# GCtoUSB_Current.net
KiCad netlist of a schematic drawn in EAGLE
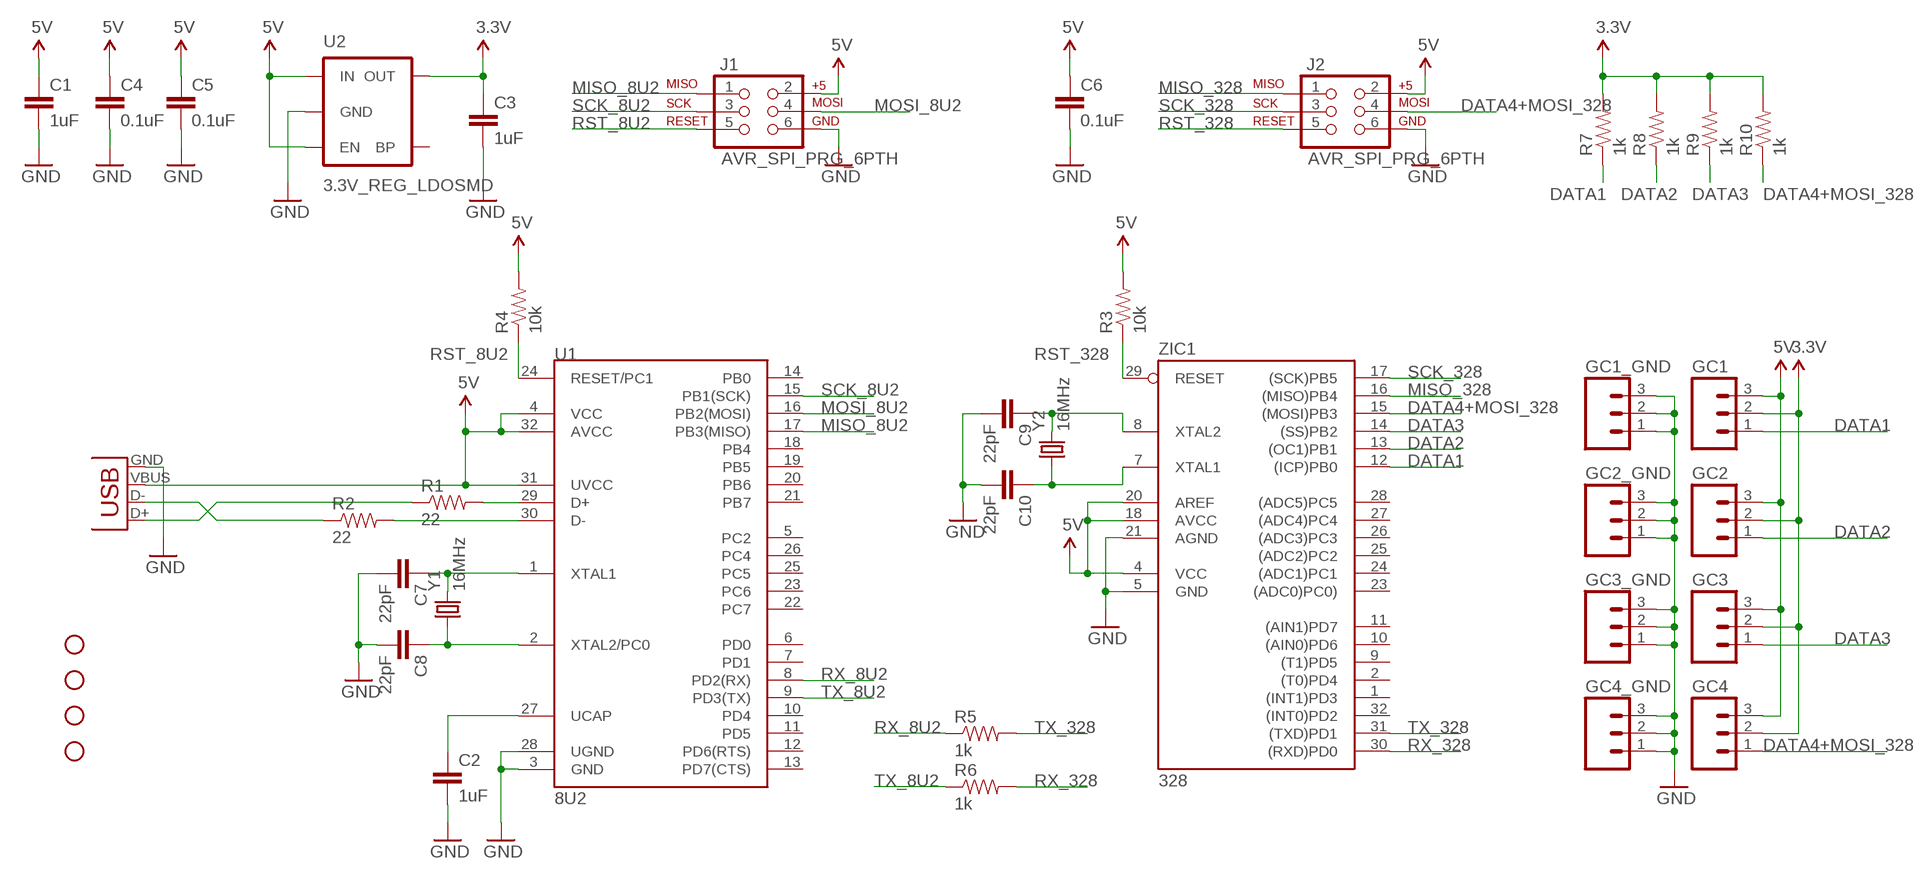
[diagram p0: schematic, sheet 1]

(export (version "E")
  (design (tool "Eeschema 10.0.6"))
  (components
    (comp (ref "C1")
      (value "1uF")
      (footprint "eagle-import:0402-CAP")
      (libsource (lib "eagle-import") (part "CAP0402-CAP"))
    )
    (comp (ref "C2")
      (value "1uF")
      (footprint "eagle-import:0402-CAP")
      (libsource (lib "eagle-import") (part "CAP0402-CAP"))
    )
    (comp (ref "C3")
      (value "1uF")
      (footprint "eagle-import:0402-CAP")
      (libsource (lib "eagle-import") (part "CAP0402-CAP"))
    )
    (comp (ref "C4")
      (value "0.1uF")
      (footprint "eagle-import:0402-CAP")
      (libsource (lib "eagle-import") (part "CAP0402-CAP"))
    )
    (comp (ref "C5")
      (value "0.1uF")
      (footprint "eagle-import:0402-CAP")
      (libsource (lib "eagle-import") (part "CAP0402-CAP"))
    )
    (comp (ref "C6")
      (value "0.1uF")
      (footprint "eagle-import:0402-CAP")
      (libsource (lib "eagle-import") (part "CAP0402-CAP"))
    )
    (comp (ref "C7")
      (value "22pF")
      (footprint "eagle-import:0402-CAP")
      (libsource (lib "eagle-import") (part "CAP0402-CAP"))
    )
    (comp (ref "C8")
      (value "22pF")
      (footprint "eagle-import:0402-CAP")
      (libsource (lib "eagle-import") (part "CAP0402-CAP"))
    )
    (comp (ref "C9")
      (value "22pF")
      (footprint "eagle-import:0402-CAP")
      (libsource (lib "eagle-import") (part "CAP0402-CAP"))
    )
    (comp (ref "C10")
      (value "22pF")
      (footprint "eagle-import:0402-CAP")
      (libsource (lib "eagle-import") (part "CAP0402-CAP"))
    )
    (comp (ref "GC1")
      (value "M031X03_NO_SILK")
      (footprint "eagle-import:1X03_NO_SILK")
      (libsource (lib "eagle-import") (part "M031X03_NO_SILK"))
    )
    (comp (ref "GC1_GND")
      (value "M031X03_NO_SILK")
      (footprint "eagle-import:1X03_NO_SILK")
      (libsource (lib "eagle-import") (part "M031X03_NO_SILK"))
    )
    (comp (ref "GC2")
      (value "M031X03_NO_SILK")
      (footprint "eagle-import:1X03_NO_SILK")
      (libsource (lib "eagle-import") (part "M031X03_NO_SILK"))
    )
    (comp (ref "GC2_GND")
      (value "M031X03_NO_SILK")
      (footprint "eagle-import:1X03_NO_SILK")
      (libsource (lib "eagle-import") (part "M031X03_NO_SILK"))
    )
    (comp (ref "GC3")
      (value "M031X03_NO_SILK")
      (footprint "eagle-import:1X03_NO_SILK")
      (libsource (lib "eagle-import") (part "M031X03_NO_SILK"))
    )
    (comp (ref "GC3_GND")
      (value "M031X03_NO_SILK")
      (footprint "eagle-import:1X03_NO_SILK")
      (libsource (lib "eagle-import") (part "M031X03_NO_SILK"))
    )
    (comp (ref "GC4")
      (value "M031X03_NO_SILK")
      (footprint "eagle-import:1X03_NO_SILK")
      (libsource (lib "eagle-import") (part "M031X03_NO_SILK"))
    )
    (comp (ref "GC4_GND")
      (value "M031X03_NO_SILK")
      (footprint "eagle-import:1X03_NO_SILK")
      (libsource (lib "eagle-import") (part "M031X03_NO_SILK"))
    )
    (comp (ref "J1")
      (value "AVR_SPI_PRG_6PTH")
      (footprint "eagle-import:2X3")
      (libsource (lib "eagle-import") (part "AVR_SPI_PRG_6PTH"))
    )
    (comp (ref "J2")
      (value "AVR_SPI_PRG_6PTH")
      (footprint "eagle-import:2X3")
      (libsource (lib "eagle-import") (part "AVR_SPI_PRG_6PTH"))
    )
    (comp (ref "JP5")
      (value "STAND-OFF")
      (footprint "eagle-import:STAND-OFF")
      (libsource (lib "eagle-import") (part "STAND-OFF"))
    )
    (comp (ref "JP6")
      (value "STAND-OFF")
      (footprint "eagle-import:STAND-OFF")
      (libsource (lib "eagle-import") (part "STAND-OFF"))
    )
    (comp (ref "JP7")
      (value "STAND-OFF")
      (footprint "eagle-import:STAND-OFF")
      (libsource (lib "eagle-import") (part "STAND-OFF"))
    )
    (comp (ref "JP8")
      (value "STAND-OFF")
      (footprint "eagle-import:STAND-OFF")
      (libsource (lib "eagle-import") (part "STAND-OFF"))
    )
    (comp (ref "R1")
      (value "22")
      (footprint "eagle-import:0603-RES")
      (libsource (lib "eagle-import") (part "RESISTOR0603-RES"))
    )
    (comp (ref "R2")
      (value "22")
      (footprint "eagle-import:0603-RES")
      (libsource (lib "eagle-import") (part "RESISTOR0603-RES"))
    )
    (comp (ref "R3")
      (value "10k")
      (footprint "eagle-import:0603-RES")
      (libsource (lib "eagle-import") (part "RESISTOR0603-RES"))
    )
    (comp (ref "R4")
      (value "10k")
      (footprint "eagle-import:0603-RES")
      (libsource (lib "eagle-import") (part "RESISTOR0603-RES"))
    )
    (comp (ref "R5")
      (value "1k")
      (footprint "eagle-import:0603-RES")
      (libsource (lib "eagle-import") (part "RESISTOR0603-RES"))
    )
    (comp (ref "R6")
      (value "1k")
      (footprint "eagle-import:0603-RES")
      (libsource (lib "eagle-import") (part "RESISTOR0603-RES"))
    )
    (comp (ref "R7")
      (value "1k")
      (footprint "eagle-import:0603-RES")
      (libsource (lib "eagle-import") (part "RESISTOR0603-RES"))
    )
    (comp (ref "R8")
      (value "1k")
      (footprint "eagle-import:0603-RES")
      (libsource (lib "eagle-import") (part "RESISTOR0603-RES"))
    )
    (comp (ref "R9")
      (value "1k")
      (footprint "eagle-import:0603-RES")
      (libsource (lib "eagle-import") (part "RESISTOR0603-RES"))
    )
    (comp (ref "R10")
      (value "1k")
      (footprint "eagle-import:0603-RES")
      (libsource (lib "eagle-import") (part "RESISTOR0603-RES"))
    )
    (comp (ref "U1")
      (value "8U2")
      (footprint "eagle-import:TQFP32-08")
      (libsource (lib "eagle-import") (part "ATMEGA8U2AU"))
    )
    (comp (ref "U2")
      (value "3.3V_REG_LDOSMD")
      (footprint "eagle-import:SOT23-5")
      (libsource (lib "eagle-import") (part "V_REG_LDOSMD"))
    )
    (comp (ref "X1")
      (value "USB-MB-H")
      (footprint "eagle-import:USB-MB-H")
      (libsource (lib "eagle-import") (part "USB-MB-H"))
    )
    (comp (ref "Y1")
      (value "16MHz")
      (footprint "eagle-import:HC49US")
      (libsource (lib "eagle-import") (part "CRYSTALHC49US"))
    )
    (comp (ref "Y2")
      (value "16MHz")
      (footprint "eagle-import:HC49US")
      (libsource (lib "eagle-import") (part "CRYSTALHC49US"))
    )
    (comp (ref "ZIC1")
      (value "328")
      (footprint "eagle-import:TQFP32-08")
      (libsource (lib "eagle-import") (part "AT90S4433A"))
    )
  )
  (nets
    (net (code "1") (name "/DATA1") (class "Default")
      (node (ref "GC1") (pin "1") (pinfunction "1_1") (pintype "passive"))
      (node (ref "R7") (pin "1") (pinfunction "1_1") (pintype "passive"))
      (node (ref "ZIC1") (pin "12") (pinfunction "(ICP)PB0_12") (pintype "bidirectional"))
    )
    (net (code "2") (name "/DATA2") (class "Default")
      (node (ref "GC2") (pin "1") (pinfunction "1_1") (pintype "passive"))
      (node (ref "R8") (pin "1") (pinfunction "1_1") (pintype "passive"))
      (node (ref "ZIC1") (pin "13") (pinfunction "(OC1)PB1_13") (pintype "bidirectional"))
    )
    (net (code "3") (name "/DATA3") (class "Default")
      (node (ref "GC3") (pin "1") (pinfunction "1_1") (pintype "passive"))
      (node (ref "R9") (pin "1") (pinfunction "1_1") (pintype "passive"))
      (node (ref "ZIC1") (pin "14") (pinfunction "(SS)PB2_14") (pintype "bidirectional"))
    )
    (net (code "4") (name "/DATA4+MOSI_328") (class "Default")
      (node (ref "GC4") (pin "1") (pinfunction "1_1") (pintype "passive"))
      (node (ref "J2") (pin "4") (pinfunction "4_4") (pintype "passive"))
      (node (ref "R10") (pin "1") (pinfunction "1_1") (pintype "passive"))
      (node (ref "ZIC1") (pin "15") (pinfunction "(MOSI)PB3_15") (pintype "bidirectional"))
    )
    (net (code "5") (name "/MISO_8U2") (class "Default")
      (node (ref "J1") (pin "1") (pinfunction "1_1") (pintype "passive"))
      (node (ref "U1") (pin "17") (pinfunction "PB3(MISO)_17") (pintype "bidirectional"))
    )
    (net (code "6") (name "/MISO_328") (class "Default")
      (node (ref "J2") (pin "1") (pinfunction "1_1") (pintype "passive"))
      (node (ref "ZIC1") (pin "16") (pinfunction "(MISO)PB4_16") (pintype "bidirectional"))
    )
    (net (code "7") (name "/MOSI_8U2") (class "Default")
      (node (ref "J1") (pin "4") (pinfunction "4_4") (pintype "passive"))
      (node (ref "U1") (pin "16") (pinfunction "PB2(MOSI)_16") (pintype "bidirectional"))
    )
    (net (code "8") (name "/RST_8U2") (class "Default")
      (node (ref "J1") (pin "5") (pinfunction "5_5") (pintype "passive"))
      (node (ref "R4") (pin "1") (pinfunction "1_1") (pintype "passive"))
      (node (ref "U1") (pin "24") (pinfunction "RESET/PC1_24") (pintype "bidirectional"))
    )
    (net (code "9") (name "/RST_328") (class "Default")
      (node (ref "J2") (pin "5") (pinfunction "5_5") (pintype "passive"))
      (node (ref "R3") (pin "1") (pinfunction "1_1") (pintype "passive"))
      (node (ref "ZIC1") (pin "29") (pinfunction "RESET_29") (pintype "input"))
    )
    (net (code "10") (name "/RX_8U2") (class "Default")
      (node (ref "R5") (pin "1") (pinfunction "1_1") (pintype "passive"))
      (node (ref "U1") (pin "8") (pinfunction "PD2(RX)_8") (pintype "bidirectional"))
    )
    (net (code "11") (name "/RX_328") (class "Default")
      (node (ref "R6") (pin "2") (pinfunction "2_2") (pintype "passive"))
      (node (ref "ZIC1") (pin "30") (pinfunction "(RXD)PD0_30") (pintype "bidirectional"))
    )
    (net (code "12") (name "/SCK_8U2") (class "Default")
      (node (ref "J1") (pin "3") (pinfunction "3_3") (pintype "passive"))
      (node (ref "U1") (pin "15") (pinfunction "PB1(SCK)_15") (pintype "bidirectional"))
    )
    (net (code "13") (name "/SCK_328") (class "Default")
      (node (ref "J2") (pin "3") (pinfunction "3_3") (pintype "passive"))
      (node (ref "ZIC1") (pin "17") (pinfunction "(SCK)PB5_17") (pintype "bidirectional"))
    )
    (net (code "14") (name "/TX_8U2") (class "Default")
      (node (ref "R6") (pin "1") (pinfunction "1_1") (pintype "passive"))
      (node (ref "U1") (pin "9") (pinfunction "PD3(TX)_9") (pintype "bidirectional"))
    )
    (net (code "15") (name "/TX_328") (class "Default")
      (node (ref "R5") (pin "2") (pinfunction "2_2") (pintype "passive"))
      (node (ref "ZIC1") (pin "31") (pinfunction "(TXD)PD1_31") (pintype "bidirectional"))
    )
    (net (code "16") (name "3.3V") (class "Default")
      (node (ref "C3") (pin "1") (pinfunction "1_1") (pintype "passive"))
      (node (ref "GC1") (pin "2") (pinfunction "2_2") (pintype "passive"))
      (node (ref "GC2") (pin "2") (pinfunction "2_2") (pintype "passive"))
      (node (ref "GC3") (pin "2") (pinfunction "2_2") (pintype "passive"))
      (node (ref "GC4") (pin "2") (pinfunction "2_2") (pintype "passive"))
      (node (ref "R10") (pin "2") (pinfunction "2_2") (pintype "passive"))
      (node (ref "R7") (pin "2") (pinfunction "2_2") (pintype "passive"))
      (node (ref "R8") (pin "2") (pinfunction "2_2") (pintype "passive"))
      (node (ref "R9") (pin "2") (pinfunction "2_2") (pintype "passive"))
      (node (ref "U2") (pin "5") (pinfunction "OUT_5") (pintype "passive"))
    )
    (net (code "17") (name "5V") (class "Default")
      (node (ref "C1") (pin "1") (pinfunction "1_1") (pintype "passive"))
      (node (ref "C4") (pin "1") (pinfunction "1_1") (pintype "passive"))
      (node (ref "C5") (pin "1") (pinfunction "1_1") (pintype "passive"))
      (node (ref "C6") (pin "1") (pinfunction "1_1") (pintype "passive"))
      (node (ref "GC1") (pin "3") (pinfunction "3_3") (pintype "passive"))
      (node (ref "GC2") (pin "3") (pinfunction "3_3") (pintype "passive"))
      (node (ref "GC3") (pin "3") (pinfunction "3_3") (pintype "passive"))
      (node (ref "GC4") (pin "3") (pinfunction "3_3") (pintype "passive"))
      (node (ref "J1") (pin "2") (pinfunction "2_2") (pintype "passive"))
      (node (ref "J2") (pin "2") (pinfunction "2_2") (pintype "passive"))
      (node (ref "R3") (pin "2") (pinfunction "2_2") (pintype "passive"))
      (node (ref "R4") (pin "2") (pinfunction "2_2") (pintype "passive"))
      (node (ref "U1") (pin "31") (pinfunction "UVCC_31") (pintype "bidirectional"))
      (node (ref "U1") (pin "32") (pinfunction "AVCC_32") (pintype "bidirectional"))
      (node (ref "U1") (pin "4") (pinfunction "VCC_4") (pintype "bidirectional"))
      (node (ref "U2") (pin "1") (pinfunction "IN_1") (pintype "input"))
      (node (ref "U2") (pin "3") (pinfunction "EN_3") (pintype "input"))
      (node (ref "X1") (pin "VBUS") (pinfunction "VBUS_VBUS") (pintype "bidirectional"))
      (node (ref "ZIC1") (pin "18") (pinfunction "AVCC_18") (pintype "power_in"))
      (node (ref "ZIC1") (pin "20") (pinfunction "AREF_20") (pintype "passive"))
      (node (ref "ZIC1") (pin "4") (pinfunction "VCC_4") (pintype "power_in"))
    )
    (net (code "18") (name "GND") (class "Default")
      (node (ref "C1") (pin "2") (pinfunction "2_2") (pintype "passive"))
      (node (ref "C10") (pin "2") (pinfunction "2_2") (pintype "passive"))
      (node (ref "C2") (pin "2") (pinfunction "2_2") (pintype "passive"))
      (node (ref "C3") (pin "2") (pinfunction "2_2") (pintype "passive"))
      (node (ref "C4") (pin "2") (pinfunction "2_2") (pintype "passive"))
      (node (ref "C5") (pin "2") (pinfunction "2_2") (pintype "passive"))
      (node (ref "C6") (pin "2") (pinfunction "2_2") (pintype "passive"))
      (node (ref "C7") (pin "2") (pinfunction "2_2") (pintype "passive"))
      (node (ref "C8") (pin "2") (pinfunction "2_2") (pintype "passive"))
      (node (ref "C9") (pin "2") (pinfunction "2_2") (pintype "passive"))
      (node (ref "GC1_GND") (pin "1") (pinfunction "1_1") (pintype "passive"))
      (node (ref "GC1_GND") (pin "2") (pinfunction "2_2") (pintype "passive"))
      (node (ref "GC1_GND") (pin "3") (pinfunction "3_3") (pintype "passive"))
      (node (ref "GC2_GND") (pin "1") (pinfunction "1_1") (pintype "passive"))
      (node (ref "GC2_GND") (pin "2") (pinfunction "2_2") (pintype "passive"))
      (node (ref "GC2_GND") (pin "3") (pinfunction "3_3") (pintype "passive"))
      (node (ref "GC3_GND") (pin "1") (pinfunction "1_1") (pintype "passive"))
      (node (ref "GC3_GND") (pin "2") (pinfunction "2_2") (pintype "passive"))
      (node (ref "GC3_GND") (pin "3") (pinfunction "3_3") (pintype "passive"))
      (node (ref "GC4_GND") (pin "1") (pinfunction "1_1") (pintype "passive"))
      (node (ref "GC4_GND") (pin "2") (pinfunction "2_2") (pintype "passive"))
      (node (ref "GC4_GND") (pin "3") (pinfunction "3_3") (pintype "passive"))
      (node (ref "J1") (pin "6") (pinfunction "6_6") (pintype "passive"))
      (node (ref "J2") (pin "6") (pinfunction "6_6") (pintype "passive"))
      (node (ref "U1") (pin "28") (pinfunction "UGND_28") (pintype "bidirectional"))
      (node (ref "U1") (pin "3") (pinfunction "GND_3") (pintype "bidirectional"))
      (node (ref "U2") (pin "2") (pinfunction "GND_2") (pintype "input"))
      (node (ref "X1") (pin "GND") (pinfunction "GND_GND") (pintype "bidirectional"))
      (node (ref "ZIC1") (pin "21") (pinfunction "AGND_21") (pintype "power_in"))
      (node (ref "ZIC1") (pin "5") (pinfunction "GND_5") (pintype "power_in"))
    )
    (net (code "19") (name "Net-(R1-Pad1)") (class "Default")
      (node (ref "R1") (pin "1") (pinfunction "1_1") (pintype "passive"))
      (node (ref "X1") (pin "D+") (pinfunction "D+_D+") (pintype "bidirectional"))
    )
    (net (code "20") (name "Net-(R2-Pad1)") (class "Default")
      (node (ref "R2") (pin "1") (pinfunction "1_1") (pintype "passive"))
      (node (ref "X1") (pin "D-") (pinfunction "D-_D-") (pintype "bidirectional"))
    )
    (net (code "21") (name "Net-(U1-D+)") (class "Default")
      (node (ref "R1") (pin "2") (pinfunction "2_2") (pintype "passive"))
      (node (ref "U1") (pin "29") (pinfunction "D+_29") (pintype "bidirectional"))
    )
    (net (code "22") (name "Net-(U1-D-)") (class "Default")
      (node (ref "R2") (pin "2") (pinfunction "2_2") (pintype "passive"))
      (node (ref "U1") (pin "30") (pinfunction "D-_30") (pintype "bidirectional"))
    )
    (net (code "23") (name "Net-(U1-UCAP)") (class "Default")
      (node (ref "C2") (pin "1") (pinfunction "1_1") (pintype "passive"))
      (node (ref "U1") (pin "27") (pinfunction "UCAP_27") (pintype "bidirectional"))
    )
    (net (code "24") (name "Net-(U1-XTAL1)") (class "Default")
      (node (ref "C7") (pin "1") (pinfunction "1_1") (pintype "passive"))
      (node (ref "U1") (pin "1") (pinfunction "XTAL1_1") (pintype "bidirectional"))
      (node (ref "Y1") (pin "2") (pinfunction "2_2") (pintype "passive"))
    )
    (net (code "25") (name "Net-(U1-XTAL2{slash}PC0)") (class "Default")
      (node (ref "C8") (pin "1") (pinfunction "1_1") (pintype "passive"))
      (node (ref "U1") (pin "2") (pinfunction "XTAL2/PC0_2") (pintype "bidirectional"))
      (node (ref "Y1") (pin "1") (pinfunction "1_1") (pintype "passive"))
    )
    (net (code "26") (name "Net-(ZIC1-XTAL1)") (class "Default")
      (node (ref "C10") (pin "1") (pinfunction "1_1") (pintype "passive"))
      (node (ref "Y2") (pin "1") (pinfunction "1_1") (pintype "passive"))
      (node (ref "ZIC1") (pin "7") (pinfunction "XTAL1_7") (pintype "bidirectional"))
    )
    (net (code "27") (name "Net-(ZIC1-XTAL2)") (class "Default")
      (node (ref "C9") (pin "1") (pinfunction "1_1") (pintype "passive"))
      (node (ref "Y2") (pin "2") (pinfunction "2_2") (pintype "passive"))
      (node (ref "ZIC1") (pin "8") (pinfunction "XTAL2_8") (pintype "bidirectional"))
    )
    (net (code "28") (name "unconnected-(U1-PB0-Pad14)") (class "Default")
      (node (ref "U1") (pin "14") (pinfunction "PB0_14") (pintype "bidirectional"))
    )
    (net (code "29") (name "unconnected-(U1-PB4-Pad18)") (class "Default")
      (node (ref "U1") (pin "18") (pinfunction "PB4_18") (pintype "bidirectional"))
    )
    (net (code "30") (name "unconnected-(U1-PB5-Pad19)") (class "Default")
      (node (ref "U1") (pin "19") (pinfunction "PB5_19") (pintype "bidirectional"))
    )
    (net (code "31") (name "unconnected-(U1-PB6-Pad20)") (class "Default")
      (node (ref "U1") (pin "20") (pinfunction "PB6_20") (pintype "bidirectional"))
    )
    (net (code "32") (name "unconnected-(U1-PB7-Pad21)") (class "Default")
      (node (ref "U1") (pin "21") (pinfunction "PB7_21") (pintype "bidirectional"))
    )
    (net (code "33") (name "unconnected-(U1-PC2-Pad5)") (class "Default")
      (node (ref "U1") (pin "5") (pinfunction "PC2_5") (pintype "bidirectional"))
    )
    (net (code "34") (name "unconnected-(U1-PC4-Pad26)") (class "Default")
      (node (ref "U1") (pin "26") (pinfunction "PC4_26") (pintype "bidirectional"))
    )
    (net (code "35") (name "unconnected-(U1-PC5-Pad25)") (class "Default")
      (node (ref "U1") (pin "25") (pinfunction "PC5_25") (pintype "bidirectional"))
    )
    (net (code "36") (name "unconnected-(U1-PC6-Pad23)") (class "Default")
      (node (ref "U1") (pin "23") (pinfunction "PC6_23") (pintype "bidirectional"))
    )
    (net (code "37") (name "unconnected-(U1-PC7-Pad22)") (class "Default")
      (node (ref "U1") (pin "22") (pinfunction "PC7_22") (pintype "bidirectional"))
    )
    (net (code "38") (name "unconnected-(U1-PD0-Pad6)") (class "Default")
      (node (ref "U1") (pin "6") (pinfunction "PD0_6") (pintype "bidirectional"))
    )
    (net (code "39") (name "unconnected-(U1-PD1-Pad7)") (class "Default")
      (node (ref "U1") (pin "7") (pinfunction "PD1_7") (pintype "bidirectional"))
    )
    (net (code "40") (name "unconnected-(U1-PD4-Pad10)") (class "Default")
      (node (ref "U1") (pin "10") (pinfunction "PD4_10") (pintype "bidirectional"))
    )
    (net (code "41") (name "unconnected-(U1-PD5-Pad11)") (class "Default")
      (node (ref "U1") (pin "11") (pinfunction "PD5_11") (pintype "bidirectional"))
    )
    (net (code "42") (name "unconnected-(U1-PD6(RTS)-Pad12)") (class "Default")
      (node (ref "U1") (pin "12") (pinfunction "PD6(RTS)_12") (pintype "bidirectional"))
    )
    (net (code "43") (name "unconnected-(U1-PD7(CTS)-Pad13)") (class "Default")
      (node (ref "U1") (pin "13") (pinfunction "PD7(CTS)_13") (pintype "bidirectional"))
    )
    (net (code "44") (name "unconnected-(U2-BP-Pad4)") (class "Default")
      (node (ref "U2") (pin "4") (pinfunction "BP_4") (pintype "input"))
    )
    (net (code "45") (name "unconnected-(ZIC1-(ADC0)PC0)-Pad23)") (class "Default")
      (node (ref "ZIC1") (pin "23") (pinfunction "(ADC0)PC0)_23") (pintype "bidirectional"))
    )
    (net (code "46") (name "unconnected-(ZIC1-(ADC1)PC1-Pad24)") (class "Default")
      (node (ref "ZIC1") (pin "24") (pinfunction "(ADC1)PC1_24") (pintype "bidirectional"))
    )
    (net (code "47") (name "unconnected-(ZIC1-(ADC2)PC2-Pad25)") (class "Default")
      (node (ref "ZIC1") (pin "25") (pinfunction "(ADC2)PC2_25") (pintype "bidirectional"))
    )
    (net (code "48") (name "unconnected-(ZIC1-(ADC3)PC3-Pad26)") (class "Default")
      (node (ref "ZIC1") (pin "26") (pinfunction "(ADC3)PC3_26") (pintype "bidirectional"))
    )
    (net (code "49") (name "unconnected-(ZIC1-(ADC4)PC4-Pad27)") (class "Default")
      (node (ref "ZIC1") (pin "27") (pinfunction "(ADC4)PC4_27") (pintype "bidirectional"))
    )
    (net (code "50") (name "unconnected-(ZIC1-(ADC5)PC5-Pad28)") (class "Default")
      (node (ref "ZIC1") (pin "28") (pinfunction "(ADC5)PC5_28") (pintype "bidirectional"))
    )
    (net (code "51") (name "unconnected-(ZIC1-(AIN0)PD6-Pad10)") (class "Default")
      (node (ref "ZIC1") (pin "10") (pinfunction "(AIN0)PD6_10") (pintype "bidirectional"))
    )
    (net (code "52") (name "unconnected-(ZIC1-(AIN1)PD7-Pad11)") (class "Default")
      (node (ref "ZIC1") (pin "11") (pinfunction "(AIN1)PD7_11") (pintype "bidirectional"))
    )
    (net (code "53") (name "unconnected-(ZIC1-(INT0)PD2-Pad32)") (class "Default")
      (node (ref "ZIC1") (pin "32") (pinfunction "(INT0)PD2_32") (pintype "bidirectional"))
    )
    (net (code "54") (name "unconnected-(ZIC1-(INT1)PD3-Pad1)") (class "Default")
      (node (ref "ZIC1") (pin "1") (pinfunction "(INT1)PD3_1") (pintype "bidirectional"))
    )
    (net (code "55") (name "unconnected-(ZIC1-(T0)PD4-Pad2)") (class "Default")
      (node (ref "ZIC1") (pin "2") (pinfunction "(T0)PD4_2") (pintype "bidirectional"))
    )
    (net (code "56") (name "unconnected-(ZIC1-(T1)PD5-Pad9)") (class "Default")
      (node (ref "ZIC1") (pin "9") (pinfunction "(T1)PD5_9") (pintype "bidirectional"))
    )
  )
)
